# -200mV_Reference_Voltage.net
KiCad netlist of a schematic drawn in Altium Designer
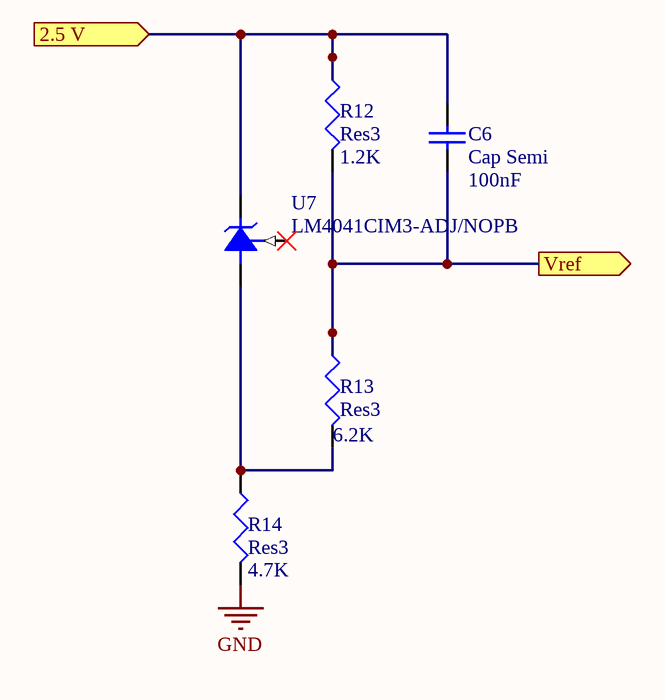
[diagram p0: -200mV_Reference_Voltage.SchDoc]

(export (version "E")
  (design (tool "Eeschema 10.0.6"))
  (components
    (comp (ref "C6")
      (value "Cap Semi")
      (footprint "C1206")
      (description "Capacitor (Semiconductor SIM Model)")
      (fields (field (name "ALTIUM_VALUE") "100nF") (field (name "PUBLISHER") "Altium Limited"))
      (libsource (lib "Miscellaneous Devices") (part "Cap Semi"))
    )
    (comp (ref "R12")
      (value "Res3")
      (footprint "J1-0603")
      (description "Resistor")
      (fields (field (name "ALTIUM_VALUE") "1.2K") (field (name "PUBLISHER") "Altium Limited"))
      (libsource (lib "Miscellaneous Devices") (part "Res3"))
    )
    (comp (ref "R13")
      (value "Res3")
      (footprint "J1-0603")
      (description "Resistor")
      (fields (field (name "ALTIUM_VALUE") "6.2K") (field (name "PUBLISHER") "Altium Limited"))
      (libsource (lib "Miscellaneous Devices") (part "Res3"))
    )
    (comp (ref "R14")
      (value "Res3")
      (footprint "J1-0603")
      (description "Resistor")
      (fields (field (name "ALTIUM_VALUE") "4.7K") (field (name "PUBLISHER") "Altium Limited"))
      (libsource (lib "Miscellaneous Devices") (part "Res3"))
    )
    (comp (ref "U7")
      (value "LM4041CIM3-ADJ/NOPB")
      (footprint "MF03A_M")
      (description "Precision Micropower Shunt Voltage Reference, 3-pin SOT-23, Pb-Free")
      (fields (field (name "MANUFACTURER") "National Semiconductor"))
      (libsource (lib "Altium Content Vault") (part "PM-REF-LM113FB-3"))
    )
  )
  (nets
    (net (code "1") (name "/2.5 V") (class "Default")
      (node (ref "C6") (pin "1") (pinfunction "1_1") (pintype "passive"))
      (node (ref "R12") (pin "2") (pinfunction "2_2") (pintype "passive"))
      (node (ref "U7") (pin "2") (pinfunction "+V_2") (pintype "passive"))
    )
    (net (code "2") (name "/Vref") (class "Default")
      (node (ref "C6") (pin "2") (pinfunction "2_2") (pintype "passive"))
      (node (ref "R12") (pin "1") (pinfunction "1_1") (pintype "passive"))
      (node (ref "R13") (pin "2") (pinfunction "2_2") (pintype "passive"))
    )
    (net (code "3") (name "GND") (class "Default")
      (node (ref "R14") (pin "1") (pinfunction "1_1") (pintype "passive"))
    )
    (net (code "4") (name "Net-(U7--V)") (class "Default")
      (node (ref "R13") (pin "1") (pinfunction "1_1") (pintype "passive"))
      (node (ref "R14") (pin "2") (pinfunction "2_2") (pintype "passive"))
      (node (ref "U7") (pin "3") (pinfunction "-V_3") (pintype "passive"))
    )
    (net (code "5") (name "unconnected-(U7-FB-Pad1)") (class "Default")
      (node (ref "U7") (pin "1") (pinfunction "FB_1") (pintype "input+no_connect"))
    )
  )
)
